# 1-Schematic_ESQUEM_TICO_UTP-100.net
KiCad netlist of a schematic drawn in EasyEDA
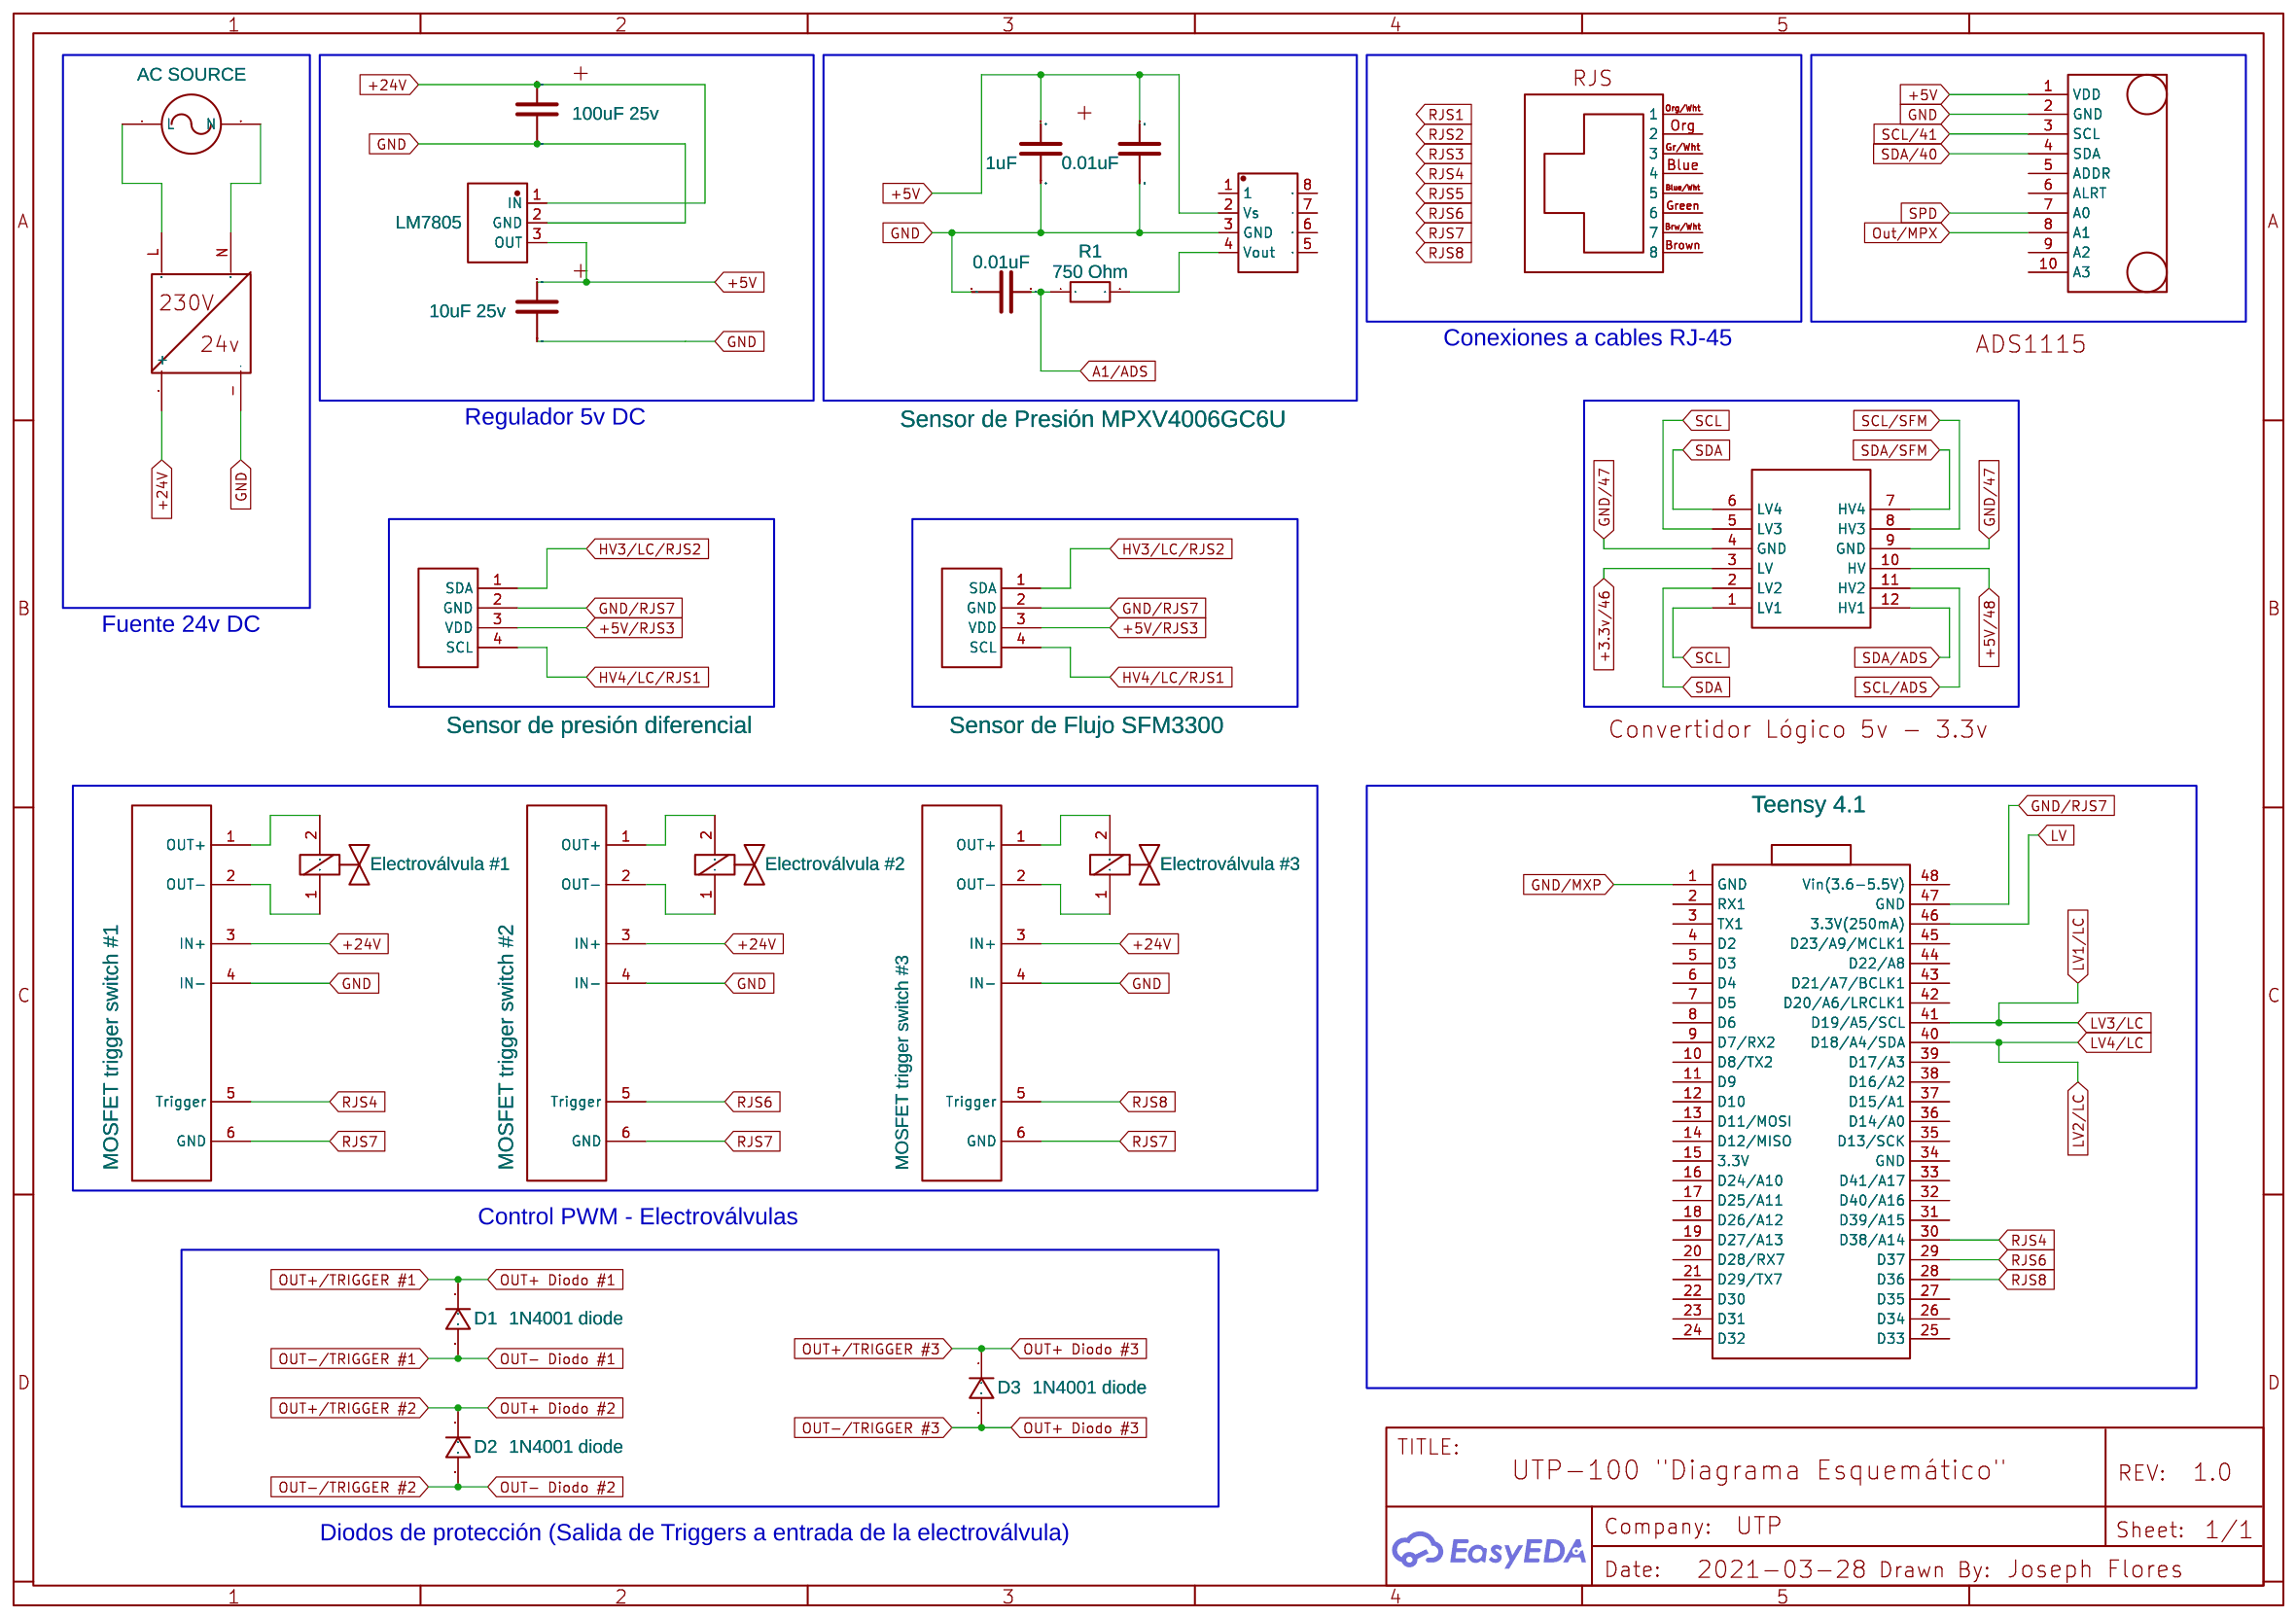
[diagram p0: schematic sheet]

(export (version "E")
  (design (tool "Eeschema 10.0.6"))
  (components
    (comp (ref "D1")
      (value "1N4001 diode")
      (fields (field (name "BOM_Manufacturer Part") "1N4007") (field (name "BOM_Supplier Part") "C331633"))
      (libsource (lib "") (part "1N4007 diode"))
    )
    (comp (ref "D2")
      (value "1N4001 diode")
      (fields (field (name "BOM_Manufacturer Part") "1N4007") (field (name "BOM_Supplier Part") "C331633"))
      (libsource (lib "") (part "1N4007 diode"))
    )
    (comp (ref "D3")
      (value "1N4001 diode")
      (fields (field (name "BOM_Manufacturer Part") "1N4007") (field (name "BOM_Supplier Part") "C331633"))
      (libsource (lib "") (part "1N4007 diode"))
    )
    (comp (ref "R1") (value "750 Ohm") (libsource (lib "") (part "R_0201_EU")))
    (comp (ref "U1")
      (value "Teensy 4.1")
      (fields (field (name "BOM_Manufacturer Part") "Teensy 3.6"))
      (libsource (lib "") (part "Teensy 4.1 TVG"))
    )
    (comp (ref "U2") (value "ADS1115") (libsource (lib "") (part "ADS1115")))
    (comp (ref "U3")
      (value "Sensor de Flujo SFM3300")
      (fields (field (name "BOM_Manufacturer Part") "SFM3000"))
      (libsource (lib "") (part "SFM3000"))
    )
    (comp (ref "U4")
      (value "Sensor de Presión MPXV4006GC6U")
      (fields
        (field (name "BOM_Manufacturer Part") "MPXV5050GC6U")
        (field (name "BOM_Supplier Part") "C16628")
      )
      (libsource (lib "") (part "MPXV5050GC6U"))
    )
    (comp (ref "U5") (value "MOSFET trigger switch #1") (libsource (lib "") (part "MOSFET trigger switch")))
    (comp (ref "U6")
      (value "4bits Logic Level Converter Module 5V 3.3V")
      (libsource (lib "") (part "4bits Logic Level Converter Module 5V 3.3V"))
    )
    (comp (ref "U7")
      (value "Sensor de presión diferencial")
      (fields (field (name "BOM_Manufacturer Part") "SFM3000"))
      (libsource (lib "") (part "SFM3000"))
    )
    (comp (ref "U8")
      (value "RJ45")
      (fields (field (name "BOM_Supplier Part") "OL-2624"))
      (libsource (lib "") (part "RJ45"))
    )
    (comp (ref "U9")
      (value "Power_supply_24v")
      (fields (field (name "BOM_Manufacturer Part") "Power supply 24v"))
      (libsource (lib "") (part "Power_supply_24v"))
    )
    (comp (ref "U10") (value "MOSFET trigger switch #2") (libsource (lib "") (part "MOSFET trigger switch")))
    (comp (ref "U11") (value "MOSFET trigger switch #3") (libsource (lib "") (part "MOSFET trigger switch")))
    (comp (ref "U12") (value "AC SOURCE") (libsource (lib "") (part "AC SOURCE")))
    (comp (ref "U13") (value "Electroválvula #1") (libsource (lib "") (part "solenoid valve")))
    (comp (ref "U14") (value "Electroválvula #2") (libsource (lib "") (part "solenoid valve")))
    (comp (ref "U15") (value "Electroválvula #3") (libsource (lib "") (part "solenoid valve")))
    (comp (ref "U17")
      (value "LM7805")
      (fields (field (name "BOM_Supplier Part") "C845394"))
      (libsource (lib "") (part "LM7805"))
    )
    (comp (ref "U19") (value "100uF 25v") (libsource (lib "") (part "CAPACITOR")))
    (comp (ref "U20") (value "10uF 25v") (libsource (lib "") (part "CAPACITOR")))
    (comp (ref "U22") (value "1uF") (libsource (lib "") (part "CAPACITOR")))
    (comp (ref "U23") (value "0.01uF") (libsource (lib "") (part "CAPACITOR_2")))
    (comp (ref "U24") (value "0.01uF") (libsource (lib "") (part "CAPACITOR_1")))
  )
  (nets
    (net (code "1") (name "+3.3v{slash}46") (class "Default")
      (node (ref "U6") (pin "3") (pinfunction "LV_3") (pintype "unspecified"))
    )
    (net (code "2") (name "+5V") (class "Default")
      (node (ref "U17") (pin "3") (pinfunction "OUT_3") (pintype "unspecified"))
      (node (ref "U2") (pin "1") (pinfunction "VDD_1") (pintype "unspecified"))
      (node (ref "U20") (pin "P$1") (pinfunction "P$1_P$1") (pintype "unspecified"))
      (node (ref "U22") (pin "P$1") (pinfunction "P$1_P$1") (pintype "unspecified"))
      (node (ref "U23") (pin "P$1") (pinfunction "P$1_P$1") (pintype "unspecified"))
      (node (ref "U4") (pin "2") (pinfunction "Vs_2") (pintype "unspecified"))
    )
    (net (code "3") (name "+5V{slash}48") (class "Default")
      (node (ref "U6") (pin "10") (pinfunction "HV_10") (pintype "unspecified"))
    )
    (net (code "4") (name "+5V{slash}RJS3") (class "Default")
      (node (ref "U3") (pin "3") (pinfunction "VDD_3") (pintype "unspecified"))
      (node (ref "U7") (pin "3") (pinfunction "VDD_3") (pintype "unspecified"))
    )
    (net (code "5") (name "+24V") (class "Default")
      (node (ref "U10") (pin "3") (pinfunction "IN+_3") (pintype "unspecified"))
      (node (ref "U11") (pin "3") (pinfunction "IN+_3") (pintype "unspecified"))
      (node (ref "U17") (pin "1") (pinfunction "IN_1") (pintype "unspecified"))
      (node (ref "U19") (pin "P$1") (pinfunction "P$1_P$1") (pintype "unspecified"))
      (node (ref "U5") (pin "3") (pinfunction "IN+_3") (pintype "unspecified"))
      (node (ref "U9") (pin "3") (pinfunction "+_3") (pintype "input"))
    )
    (net (code "6") (name "A1{slash}ADS") (class "Default")
      (node (ref "R1") (pin "1") (pinfunction "1_1") (pintype "unspecified"))
      (node (ref "U24") (pin "P$1") (pinfunction "P$1_P$1") (pintype "unspecified"))
    )
    (net (code "7") (name "GND") (class "Default")
      (node (ref "U10") (pin "4") (pinfunction "IN-_4") (pintype "unspecified"))
      (node (ref "U11") (pin "4") (pinfunction "IN-_4") (pintype "unspecified"))
      (node (ref "U17") (pin "2") (pinfunction "GND_2") (pintype "unspecified"))
      (node (ref "U19") (pin "P$2") (pinfunction "P$2_P$2") (pintype "unspecified"))
      (node (ref "U2") (pin "2") (pinfunction "GND_2") (pintype "unspecified"))
      (node (ref "U20") (pin "P$2") (pinfunction "P$2_P$2") (pintype "unspecified"))
      (node (ref "U22") (pin "P$2") (pinfunction "P$2_P$2") (pintype "unspecified"))
      (node (ref "U23") (pin "P$2") (pinfunction "P$2_P$2") (pintype "unspecified"))
      (node (ref "U24") (pin "P$2") (pinfunction "P$2_P$2") (pintype "unspecified"))
      (node (ref "U4") (pin "3") (pinfunction "GND_3") (pintype "unspecified"))
      (node (ref "U5") (pin "4") (pinfunction "IN-_4") (pintype "unspecified"))
      (node (ref "U9") (pin "-") (pinfunction "-_-") (pintype "input"))
    )
    (net (code "8") (name "GND{slash}47") (class "Default")
      (node (ref "U6") (pin "4") (pinfunction "GND_4") (pintype "unspecified"))
      (node (ref "U6") (pin "9") (pinfunction "GND_9") (pintype "unspecified"))
    )
    (net (code "9") (name "GND{slash}MXP") (class "Default")
      (node (ref "U1") (pin "1") (pinfunction "GND_1") (pintype "unspecified"))
    )
    (net (code "10") (name "GND{slash}RJS7") (class "Default")
      (node (ref "U1") (pin "47") (pinfunction "GND_47") (pintype "unspecified"))
      (node (ref "U3") (pin "2") (pinfunction "GND_2") (pintype "unspecified"))
      (node (ref "U7") (pin "2") (pinfunction "GND_2") (pintype "unspecified"))
    )
    (net (code "11") (name "HV3{slash}LC{slash}RJS2") (class "Default")
      (node (ref "U3") (pin "1") (pinfunction "SDA_1") (pintype "unspecified"))
      (node (ref "U7") (pin "1") (pinfunction "SDA_1") (pintype "unspecified"))
    )
    (net (code "12") (name "HV4{slash}LC{slash}RJS1") (class "Default")
      (node (ref "U3") (pin "4") (pinfunction "SCL_4") (pintype "unspecified"))
      (node (ref "U7") (pin "4") (pinfunction "SCL_4") (pintype "unspecified"))
    )
    (net (code "13") (name "LV") (class "Default")
      (node (ref "U1") (pin "46") (pinfunction "3.3V(250mA)_46") (pintype "unspecified"))
    )
    (net (code "14") (name "LV1{slash}LC") (class "Default")
      (node (ref "U1") (pin "41") (pinfunction "D19/A5/SCL_41") (pintype "unspecified"))
    )
    (net (code "15") (name "LV2{slash}LC") (class "Default")
      (node (ref "U1") (pin "40") (pinfunction "D18/A4/SDA_40") (pintype "unspecified"))
    )
    (net (code "16") (name "Net-(U4-Vout)") (class "Default")
      (node (ref "R1") (pin "2") (pinfunction "2_2") (pintype "unspecified"))
      (node (ref "U4") (pin "4") (pinfunction "Vout_4") (pintype "unspecified"))
    )
    (net (code "17") (name "Net-(U5-OUT+)") (class "Default")
      (node (ref "U13") (pin "2") (pinfunction "2_2") (pintype "unspecified"))
      (node (ref "U5") (pin "1") (pinfunction "OUT+_1") (pintype "unspecified"))
    )
    (net (code "18") (name "Net-(U5-OUT-)") (class "Default")
      (node (ref "U13") (pin "1") (pinfunction "1_1") (pintype "unspecified"))
      (node (ref "U5") (pin "2") (pinfunction "OUT-_2") (pintype "unspecified"))
    )
    (net (code "19") (name "Net-(U10-OUT+)") (class "Default")
      (node (ref "U10") (pin "1") (pinfunction "OUT+_1") (pintype "unspecified"))
      (node (ref "U14") (pin "2") (pinfunction "2_2") (pintype "unspecified"))
    )
    (net (code "20") (name "Net-(U10-OUT-)") (class "Default")
      (node (ref "U10") (pin "2") (pinfunction "OUT-_2") (pintype "unspecified"))
      (node (ref "U14") (pin "1") (pinfunction "1_1") (pintype "unspecified"))
    )
    (net (code "21") (name "Net-(U11-OUT+)") (class "Default")
      (node (ref "U11") (pin "1") (pinfunction "OUT+_1") (pintype "unspecified"))
      (node (ref "U15") (pin "2") (pinfunction "2_2") (pintype "unspecified"))
    )
    (net (code "22") (name "Net-(U11-OUT-)") (class "Default")
      (node (ref "U11") (pin "2") (pinfunction "OUT-_2") (pintype "unspecified"))
      (node (ref "U15") (pin "1") (pinfunction "1_1") (pintype "unspecified"))
    )
    (net (code "23") (name "Net-(U12-L)") (class "Default")
      (node (ref "U12") (pin "1") (pinfunction "L_1") (pintype "unspecified"))
      (node (ref "U9") (pin "L") (pinfunction "pe_L") (pintype "unspecified"))
    )
    (net (code "24") (name "Net-(U12-N)") (class "Default")
      (node (ref "U12") (pin "2") (pinfunction "N_2") (pintype "unspecified"))
      (node (ref "U9") (pin "N") (pinfunction "3_N") (pintype "unspecified"))
    )
    (net (code "25") (name "OUT+ Diodo #1") (class "Default")
      (node (ref "D1") (pin "1") (pinfunction "1_1") (pintype "unspecified"))
    )
    (net (code "26") (name "OUT+ Diodo #2") (class "Default")
      (node (ref "D2") (pin "1") (pinfunction "1_1") (pintype "unspecified"))
    )
    (net (code "27") (name "OUT+ Diodo #3") (class "Default")
      (node (ref "D3") (pin "1") (pinfunction "1_1") (pintype "unspecified"))
      (node (ref "D3") (pin "2") (pinfunction "2_2") (pintype "unspecified"))
    )
    (net (code "28") (name "OUT- Diodo #1") (class "Default")
      (node (ref "D1") (pin "2") (pinfunction "2_2") (pintype "unspecified"))
    )
    (net (code "29") (name "OUT- Diodo #2") (class "Default")
      (node (ref "D2") (pin "2") (pinfunction "2_2") (pintype "unspecified"))
    )
    (net (code "30") (name "Out{slash}MPX") (class "Default")
      (node (ref "U2") (pin "8") (pinfunction "A1_8") (pintype "unspecified"))
    )
    (net (code "34") (name "RJS4") (class "Default")
      (node (ref "U1") (pin "30") (pinfunction "D38/A14_30") (pintype "unspecified"))
      (node (ref "U5") (pin "5") (pinfunction "Trigger_5") (pintype "unspecified"))
    )
    (net (code "36") (name "RJS6") (class "Default")
      (node (ref "U1") (pin "29") (pinfunction "D37_29") (pintype "unspecified"))
      (node (ref "U10") (pin "5") (pinfunction "Trigger_5") (pintype "unspecified"))
    )
    (net (code "37") (name "RJS7") (class "Default")
      (node (ref "U10") (pin "6") (pinfunction "GND_6") (pintype "unspecified"))
      (node (ref "U11") (pin "6") (pinfunction "GND_6") (pintype "unspecified"))
      (node (ref "U5") (pin "6") (pinfunction "GND_6") (pintype "unspecified"))
    )
    (net (code "38") (name "RJS8") (class "Default")
      (node (ref "U1") (pin "28") (pinfunction "D36_28") (pintype "unspecified"))
      (node (ref "U11") (pin "5") (pinfunction "Trigger_5") (pintype "unspecified"))
    )
    (net (code "39") (name "SCL") (class "Default")
      (node (ref "U6") (pin "1") (pinfunction "LV1_1") (pintype "unspecified"))
      (node (ref "U6") (pin "5") (pinfunction "LV3_5") (pintype "unspecified"))
    )
    (net (code "40") (name "SCL{slash}41") (class "Default")
      (node (ref "U2") (pin "3") (pinfunction "SCL_3") (pintype "unspecified"))
    )
    (net (code "41") (name "SCL{slash}ADS") (class "Default")
      (node (ref "U6") (pin "11") (pinfunction "HV2_11") (pintype "unspecified"))
    )
    (net (code "42") (name "SCL{slash}SFM") (class "Default")
      (node (ref "U6") (pin "8") (pinfunction "HV3_8") (pintype "unspecified"))
    )
    (net (code "43") (name "SDA") (class "Default")
      (node (ref "U6") (pin "2") (pinfunction "LV2_2") (pintype "unspecified"))
      (node (ref "U6") (pin "6") (pinfunction "LV4_6") (pintype "unspecified"))
    )
    (net (code "44") (name "SDA{slash}40") (class "Default")
      (node (ref "U2") (pin "4") (pinfunction "SDA_4") (pintype "unspecified"))
    )
    (net (code "45") (name "SDA{slash}ADS") (class "Default")
      (node (ref "U6") (pin "12") (pinfunction "HV1_12") (pintype "unspecified"))
    )
    (net (code "46") (name "SDA{slash}SFM") (class "Default")
      (node (ref "U6") (pin "7") (pinfunction "HV4_7") (pintype "unspecified"))
    )
    (net (code "47") (name "SPD") (class "Default")
      (node (ref "U2") (pin "7") (pinfunction "A0_7") (pintype "unspecified"))
    )
    (net (code "48") (name "unconnected-(U1-3.3V-Pad15)") (class "Default")
      (node (ref "U1") (pin "15") (pinfunction "3.3V_15") (pintype "unspecified"))
    )
    (net (code "49") (name "unconnected-(U1-D2-Pad4)") (class "Default")
      (node (ref "U1") (pin "4") (pinfunction "D2_4") (pintype "unspecified"))
    )
    (net (code "50") (name "unconnected-(U1-D3-Pad5)") (class "Default")
      (node (ref "U1") (pin "5") (pinfunction "D3_5") (pintype "unspecified"))
    )
    (net (code "51") (name "unconnected-(U1-D4-Pad6)") (class "Default")
      (node (ref "U1") (pin "6") (pinfunction "D4_6") (pintype "unspecified"))
    )
    (net (code "52") (name "unconnected-(U1-D5-Pad7)") (class "Default")
      (node (ref "U1") (pin "7") (pinfunction "D5_7") (pintype "unspecified"))
    )
    (net (code "53") (name "unconnected-(U1-D6-Pad8)") (class "Default")
      (node (ref "U1") (pin "8") (pinfunction "D6_8") (pintype "unspecified"))
    )
    (net (code "54") (name "unconnected-(U1-D7{slash}RX2-Pad9)") (class "Default")
      (node (ref "U1") (pin "9") (pinfunction "D7/RX2_9") (pintype "unspecified"))
    )
    (net (code "55") (name "unconnected-(U1-D8{slash}TX2-Pad10)") (class "Default")
      (node (ref "U1") (pin "10") (pinfunction "D8/TX2_10") (pintype "unspecified"))
    )
    (net (code "56") (name "unconnected-(U1-D9-Pad11)") (class "Default")
      (node (ref "U1") (pin "11") (pinfunction "D9_11") (pintype "unspecified"))
    )
    (net (code "57") (name "unconnected-(U1-D10-Pad12)") (class "Default")
      (node (ref "U1") (pin "12") (pinfunction "D10_12") (pintype "unspecified"))
    )
    (net (code "58") (name "unconnected-(U1-D11{slash}MOSI-Pad13)") (class "Default")
      (node (ref "U1") (pin "13") (pinfunction "D11/MOSI_13") (pintype "unspecified"))
    )
    (net (code "59") (name "unconnected-(U1-D12{slash}MISO-Pad14)") (class "Default")
      (node (ref "U1") (pin "14") (pinfunction "D12/MISO_14") (pintype "unspecified"))
    )
    (net (code "60") (name "unconnected-(U1-D13{slash}SCK-Pad35)") (class "Default")
      (node (ref "U1") (pin "35") (pinfunction "D13/SCK_35") (pintype "unspecified"))
    )
    (net (code "61") (name "unconnected-(U1-D14{slash}A0-Pad36)") (class "Default")
      (node (ref "U1") (pin "36") (pinfunction "D14/A0_36") (pintype "unspecified"))
    )
    (net (code "62") (name "unconnected-(U1-D15{slash}A1-Pad37)") (class "Default")
      (node (ref "U1") (pin "37") (pinfunction "D15/A1_37") (pintype "unspecified"))
    )
    (net (code "63") (name "unconnected-(U1-D16{slash}A2-Pad38)") (class "Default")
      (node (ref "U1") (pin "38") (pinfunction "D16/A2_38") (pintype "unspecified"))
    )
    (net (code "64") (name "unconnected-(U1-D17{slash}A3-Pad39)") (class "Default")
      (node (ref "U1") (pin "39") (pinfunction "D17/A3_39") (pintype "unspecified"))
    )
    (net (code "65") (name "unconnected-(U1-D20{slash}A6{slash}LRCLK1-Pad42)") (class "Default")
      (node (ref "U1") (pin "42") (pinfunction "D20/A6/LRCLK1_42") (pintype "unspecified"))
    )
    (net (code "66") (name "unconnected-(U1-D21{slash}A7{slash}BCLK1-Pad43)") (class "Default")
      (node (ref "U1") (pin "43") (pinfunction "D21/A7/BCLK1_43") (pintype "unspecified"))
    )
    (net (code "67") (name "unconnected-(U1-D22{slash}A8-Pad44)") (class "Default")
      (node (ref "U1") (pin "44") (pinfunction "D22/A8_44") (pintype "unspecified"))
    )
    (net (code "68") (name "unconnected-(U1-D23{slash}A9{slash}MCLK1-Pad45)") (class "Default")
      (node (ref "U1") (pin "45") (pinfunction "D23/A9/MCLK1_45") (pintype "unspecified"))
    )
    (net (code "69") (name "unconnected-(U1-D24{slash}A10-Pad16)") (class "Default")
      (node (ref "U1") (pin "16") (pinfunction "D24/A10_16") (pintype "unspecified"))
    )
    (net (code "70") (name "unconnected-(U1-D25{slash}A11-Pad17)") (class "Default")
      (node (ref "U1") (pin "17") (pinfunction "D25/A11_17") (pintype "unspecified"))
    )
    (net (code "71") (name "unconnected-(U1-D26{slash}A12-Pad18)") (class "Default")
      (node (ref "U1") (pin "18") (pinfunction "D26/A12_18") (pintype "unspecified"))
    )
    (net (code "72") (name "unconnected-(U1-D27{slash}A13-Pad19)") (class "Default")
      (node (ref "U1") (pin "19") (pinfunction "D27/A13_19") (pintype "unspecified"))
    )
    (net (code "73") (name "unconnected-(U1-D28{slash}RX7-Pad20)") (class "Default")
      (node (ref "U1") (pin "20") (pinfunction "D28/RX7_20") (pintype "unspecified"))
    )
    (net (code "74") (name "unconnected-(U1-D29{slash}TX7-Pad21)") (class "Default")
      (node (ref "U1") (pin "21") (pinfunction "D29/TX7_21") (pintype "unspecified"))
    )
    (net (code "75") (name "unconnected-(U1-D30-Pad22)") (class "Default")
      (node (ref "U1") (pin "22") (pinfunction "D30_22") (pintype "unspecified"))
    )
    (net (code "76") (name "unconnected-(U1-D31-Pad23)") (class "Default")
      (node (ref "U1") (pin "23") (pinfunction "D31_23") (pintype "unspecified"))
    )
    (net (code "77") (name "unconnected-(U1-D32-Pad24)") (class "Default")
      (node (ref "U1") (pin "24") (pinfunction "D32_24") (pintype "unspecified"))
    )
    (net (code "78") (name "unconnected-(U1-D33-Pad25)") (class "Default")
      (node (ref "U1") (pin "25") (pinfunction "D33_25") (pintype "unspecified"))
    )
    (net (code "79") (name "unconnected-(U1-D34-Pad26)") (class "Default")
      (node (ref "U1") (pin "26") (pinfunction "D34_26") (pintype "unspecified"))
    )
    (net (code "80") (name "unconnected-(U1-D35-Pad27)") (class "Default")
      (node (ref "U1") (pin "27") (pinfunction "D35_27") (pintype "unspecified"))
    )
    (net (code "81") (name "unconnected-(U1-D39{slash}A15-Pad31)") (class "Default")
      (node (ref "U1") (pin "31") (pinfunction "D39/A15_31") (pintype "unspecified"))
    )
    (net (code "82") (name "unconnected-(U1-D40{slash}A16-Pad32)") (class "Default")
      (node (ref "U1") (pin "32") (pinfunction "D40/A16_32") (pintype "unspecified"))
    )
    (net (code "83") (name "unconnected-(U1-D41{slash}A17-Pad33)") (class "Default")
      (node (ref "U1") (pin "33") (pinfunction "D41/A17_33") (pintype "unspecified"))
    )
    (net (code "84") (name "unconnected-(U1-GND-Pad34)") (class "Default")
      (node (ref "U1") (pin "34") (pinfunction "GND_34") (pintype "unspecified"))
    )
    (net (code "85") (name "unconnected-(U1-RX1-Pad2)") (class "Default")
      (node (ref "U1") (pin "2") (pinfunction "RX1_2") (pintype "unspecified"))
    )
    (net (code "86") (name "unconnected-(U1-TX1-Pad3)") (class "Default")
      (node (ref "U1") (pin "3") (pinfunction "TX1_3") (pintype "unspecified"))
    )
    (net (code "87") (name "unconnected-(U1-Vin(3.6-5.5V)-Pad48)") (class "Default")
      (node (ref "U1") (pin "48") (pinfunction "Vin(3.6-5.5V)_48") (pintype "unspecified"))
    )
    (net (code "88") (name "unconnected-(U2-A2-Pad9)") (class "Default")
      (node (ref "U2") (pin "9") (pinfunction "A2_9") (pintype "unspecified"))
    )
    (net (code "89") (name "unconnected-(U2-A3-Pad10)") (class "Default")
      (node (ref "U2") (pin "10") (pinfunction "A3_10") (pintype "unspecified"))
    )
    (net (code "90") (name "unconnected-(U2-ADDR-Pad5)") (class "Default")
      (node (ref "U2") (pin "5") (pinfunction "ADDR_5") (pintype "unspecified"))
    )
    (net (code "91") (name "unconnected-(U2-ALRT-Pad6)") (class "Default")
      (node (ref "U2") (pin "6") (pinfunction "ALRT_6") (pintype "unspecified"))
    )
    (net (code "92") (name "unconnected-(U4-Pad1)") (class "Default")
      (node (ref "U4") (pin "1") (pinfunction "1_1") (pintype "unspecified"))
    )
    (net (code "93") (name "unconnected-(U4-Pad5)") (class "Default")
      (node (ref "U4") (pin "5") (pinfunction "5_5") (pintype "unspecified"))
    )
    (net (code "94") (name "unconnected-(U4-Pad6)") (class "Default")
      (node (ref "U4") (pin "6") (pinfunction "6_6") (pintype "unspecified"))
    )
    (net (code "95") (name "unconnected-(U4-Pad7)") (class "Default")
      (node (ref "U4") (pin "7") (pinfunction "7_7") (pintype "unspecified"))
    )
    (net (code "96") (name "unconnected-(U4-Pad8)") (class "Default")
      (node (ref "U4") (pin "8") (pinfunction "8_8") (pintype "unspecified"))
    )
    (net (code "97") (name "unconnected-(U8-1-PadOrg{slash}Wht)") (class "Default")
      (node (ref "U8") (pin "Org/Wht") (pinfunction "1_Org/Wht") (pintype "bidirectional"))
    )
    (net (code "98") (name "unconnected-(U8-2-PadOrg)") (class "Default")
      (node (ref "U8") (pin "Org") (pinfunction "2_Org") (pintype "bidirectional"))
    )
    (net (code "99") (name "unconnected-(U8-3-PadGr{slash}Wht)") (class "Default")
      (node (ref "U8") (pin "Gr/Wht") (pinfunction "3_Gr/Wht") (pintype "bidirectional"))
    )
    (net (code "100") (name "unconnected-(U8-4-PadBlue)") (class "Default")
      (node (ref "U8") (pin "Blue") (pinfunction "4_Blue") (pintype "bidirectional"))
    )
    (net (code "101") (name "unconnected-(U8-5-PadBlue{slash}Wht)") (class "Default")
      (node (ref "U8") (pin "Blue/Wht") (pinfunction "5_Blue/Wht") (pintype "bidirectional"))
    )
    (net (code "102") (name "unconnected-(U8-6-PadGreen)") (class "Default")
      (node (ref "U8") (pin "Green") (pinfunction "6_Green") (pintype "bidirectional"))
    )
    (net (code "103") (name "unconnected-(U8-7-PadBrw{slash}Wht)") (class "Default")
      (node (ref "U8") (pin "Brw/Wht") (pinfunction "7_Brw/Wht") (pintype "bidirectional"))
    )
    (net (code "104") (name "unconnected-(U8-8-PadBrown)") (class "Default")
      (node (ref "U8") (pin "Brown") (pinfunction "8_Brown") (pintype "bidirectional"))
    )
  )
)
